# Solenoid_Driver_-_Single.net
KiCad netlist of a schematic drawn in EAGLE
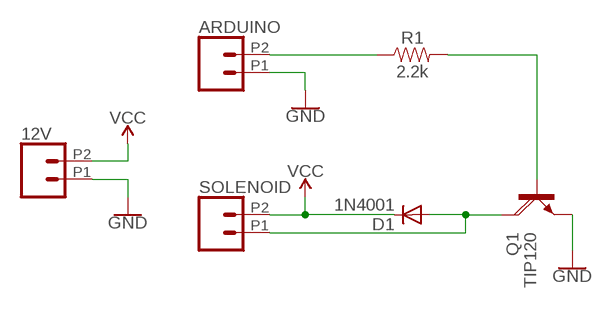
[diagram p0: schematic, sheet 1]

(export (version "E")
  (design (tool "Eeschema 10.0.6"))
  (components
    (comp (ref "12V")
      (value "CONN_022.54MM_SCREWTERM")
      (footprint "eagle-import:1X02_2.54_SCREWTERM")
      (libsource (lib "eagle-import") (part "CONN_022.54MM_SCREWTERM"))
    )
    (comp (ref "ARDUINO")
      (value "CONN_022.54MM_SCREWTERM")
      (footprint "eagle-import:1X02_2.54_SCREWTERM")
      (libsource (lib "eagle-import") (part "CONN_022.54MM_SCREWTERM"))
    )
    (comp (ref "D1")
      (value "1N4001")
      (footprint "eagle-import:DO41-10")
      (libsource (lib "eagle-import") (part "1N4004"))
    )
    (comp (ref "Q1")
      (value "TIP120")
      (footprint "eagle-import:TO220AH")
      (libsource (lib "eagle-import") (part "TIP120"))
    )
    (comp (ref "R1")
      (value "2.2k")
      (footprint "eagle-import:AXIAL-0.3-KIT")
      (libsource (lib "eagle-import") (part "10KOHM-HORIZ_KIT-1/4W-1%"))
    )
    (comp (ref "SOLENOID")
      (value "CONN_022.54MM_SCREWTERM")
      (footprint "eagle-import:1X02_2.54_SCREWTERM")
      (libsource (lib "eagle-import") (part "CONN_022.54MM_SCREWTERM"))
    )
  )
  (nets
    (net (code "1") (name "GND") (class "Default")
      (node (ref "12V") (pin "P1") (pinfunction "1_P1") (pintype "passive"))
      (node (ref "ARDUINO") (pin "P1") (pinfunction "1_P1") (pintype "passive"))
      (node (ref "Q1") (pin "E") (pinfunction "E_E") (pintype "passive"))
    )
    (net (code "2") (name "Net-(ARDUINO-2)") (class "Default")
      (node (ref "ARDUINO") (pin "P2") (pinfunction "2_P2") (pintype "passive"))
      (node (ref "R1") (pin "P$1") (pinfunction "1_P$1") (pintype "passive"))
    )
    (net (code "3") (name "Net-(R1-2)") (class "Default")
      (node (ref "Q1") (pin "B") (pinfunction "B_B") (pintype "passive"))
      (node (ref "R1") (pin "P$2") (pinfunction "2_P$2") (pintype "passive"))
    )
    (net (code "4") (name "Net-(SOLENOID-1)") (class "Default")
      (node (ref "D1") (pin "A") (pinfunction "A_A") (pintype "passive"))
      (node (ref "Q1") (pin "C") (pinfunction "C_C") (pintype "passive"))
      (node (ref "SOLENOID") (pin "P1") (pinfunction "1_P1") (pintype "passive"))
    )
    (net (code "5") (name "VCC") (class "Default")
      (node (ref "12V") (pin "P2") (pinfunction "2_P2") (pintype "passive"))
      (node (ref "D1") (pin "C") (pinfunction "C_C") (pintype "passive"))
      (node (ref "SOLENOID") (pin "P2") (pinfunction "2_P2") (pintype "passive"))
    )
  )
)
